# Relay_Board_A.net
KiCad netlist of a schematic drawn in EAGLE
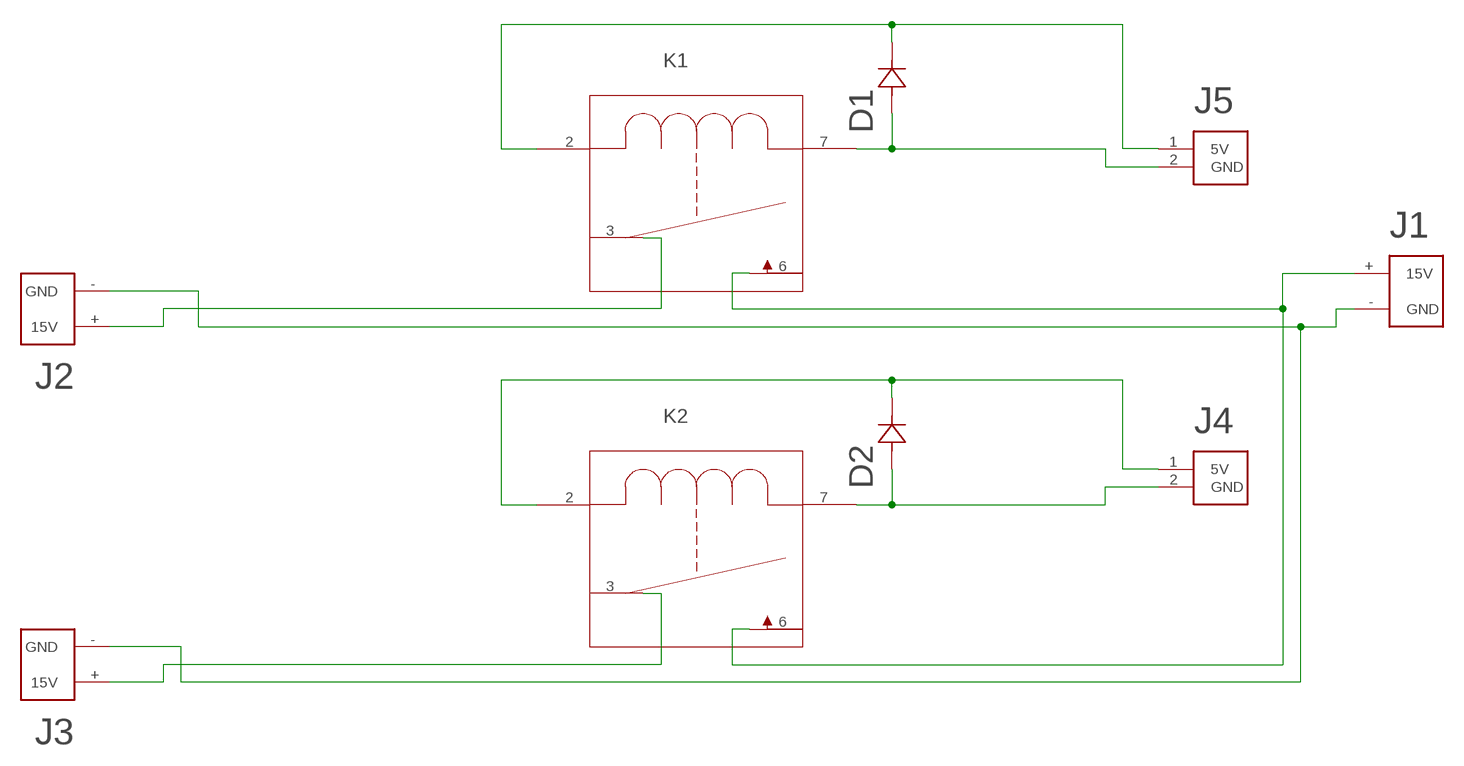
[diagram p0: schematic, sheet 1]

(export (version "E")
  (design (tool "Eeschema 10.0.6"))
  (components
    (comp (ref "D1")
      (value "1N4148W-7-FSOD123-M")
      (footprint "eagle-import:SOD123-M")
      (fields
        (field (name "MANUFACTURER_PART_NUMBER") "1N4148W7F")
        (field (name "COPYRIGHT") "Copyright C 2015 Accelerated Designs. All rights reserved")
      )
      (libsource (lib "eagle-import") (part "1N4148W-7-FSOD123-M"))
    )
    (comp (ref "D2")
      (value "1N4148W-7-FSOD123-M")
      (footprint "eagle-import:SOD123-M")
      (fields
        (field (name "MANUFACTURER_PART_NUMBER") "1N4148W7F")
        (field (name "COPYRIGHT") "Copyright C 2015 Accelerated Designs. All rights reserved")
      )
      (libsource (lib "eagle-import") (part "1N4148W-7-FSOD123-M"))
    )
    (comp (ref "J1")
      (value "ESC_CONTACTS")
      (footprint "eagle-import:XT60_CONNECTOR")
      (libsource (lib "eagle-import") (part "ESC_CONTACTS"))
    )
    (comp (ref "J2")
      (value "ESC_CONTACTS")
      (footprint "eagle-import:XT60_CONNECTOR")
      (libsource (lib "eagle-import") (part "ESC_CONTACTS"))
    )
    (comp (ref "J3")
      (value "ESC_CONTACTS")
      (footprint "eagle-import:XT60_CONNECTOR")
      (libsource (lib "eagle-import") (part "ESC_CONTACTS"))
    )
    (comp (ref "J4")
      (value "POWER_CONNECTOR")
      (footprint "eagle-import:XH_CONNECTOR")
      (libsource (lib "eagle-import") (part "POWER_CONNECTOR"))
    )
    (comp (ref "J5")
      (value "POWER_CONNECTOR")
      (footprint "eagle-import:XH_CONNECTOR")
      (libsource (lib "eagle-import") (part "POWER_CONNECTOR"))
    )
    (comp (ref "K1")
      (value "T9AS1D12-24")
      (footprint "eagle-import:RELAY_T9AS")
      (fields
        (field (name "MANUFACTURER_PART_NUMBER") "T9AS1D1224")
        (field (name "COPYRIGHT") "Copyright C 2015 Accelerated Designs. All rights reserved")
      )
      (libsource (lib "eagle-import") (part "T9AS1D12-24"))
    )
    (comp (ref "K2")
      (value "T9AS1D12-24")
      (footprint "eagle-import:RELAY_T9AS")
      (fields
        (field (name "MANUFACTURER_PART_NUMBER") "T9AS1D1224")
        (field (name "COPYRIGHT") "Copyright C 2015 Accelerated Designs. All rights reserved")
      )
      (libsource (lib "eagle-import") (part "T9AS1D12-24"))
    )
  )
  (nets
    (net (code "1") (name "Net-(D1-12)") (class "Default")
      (node (ref "D1") (pin "C") (pinfunction "12_C") (pintype "passive"))
      (node (ref "J5") (pin "1") (pinfunction "5V_1") (pintype "power_in"))
      (node (ref "K1") (pin "2") (pinfunction "1_2") (pintype "passive"))
    )
    (net (code "2") (name "Net-(D1-21)") (class "Default")
      (node (ref "D1") (pin "A") (pinfunction "21_A") (pintype "passive"))
      (node (ref "J5") (pin "2") (pinfunction "GND_2") (pintype "power_in"))
      (node (ref "K1") (pin "7") (pinfunction "4_7") (pintype "passive"))
    )
    (net (code "3") (name "Net-(D2-12)") (class "Default")
      (node (ref "D2") (pin "C") (pinfunction "12_C") (pintype "passive"))
      (node (ref "J4") (pin "1") (pinfunction "5V_1") (pintype "power_in"))
      (node (ref "K2") (pin "2") (pinfunction "1_2") (pintype "passive"))
    )
    (net (code "4") (name "Net-(D2-21)") (class "Default")
      (node (ref "D2") (pin "A") (pinfunction "21_A") (pintype "passive"))
      (node (ref "J4") (pin "2") (pinfunction "GND_2") (pintype "power_in"))
      (node (ref "K2") (pin "7") (pinfunction "4_7") (pintype "passive"))
    )
    (net (code "5") (name "Net-(J1-15V)") (class "Default")
      (node (ref "J1") (pin "+") (pinfunction "15V_+") (pintype "power_in"))
      (node (ref "K1") (pin "6") (pinfunction "3_6") (pintype "passive"))
      (node (ref "K2") (pin "6") (pinfunction "3_6") (pintype "passive"))
    )
    (net (code "6") (name "Net-(J1-GND)") (class "Default")
      (node (ref "J1") (pin "-") (pinfunction "GND_-") (pintype "power_in"))
      (node (ref "J2") (pin "-") (pinfunction "GND_-") (pintype "power_in"))
      (node (ref "J3") (pin "-") (pinfunction "GND_-") (pintype "power_in"))
    )
    (net (code "7") (name "Net-(J2-15V)") (class "Default")
      (node (ref "J2") (pin "+") (pinfunction "15V_+") (pintype "power_in"))
      (node (ref "K1") (pin "3") (pinfunction "2_3") (pintype "passive"))
    )
    (net (code "8") (name "Net-(J3-15V)") (class "Default")
      (node (ref "J3") (pin "+") (pinfunction "15V_+") (pintype "power_in"))
      (node (ref "K2") (pin "3") (pinfunction "2_3") (pintype "passive"))
    )
  )
)
